# Power-Controller.net
KiCad netlist of a schematic drawn in EAGLE
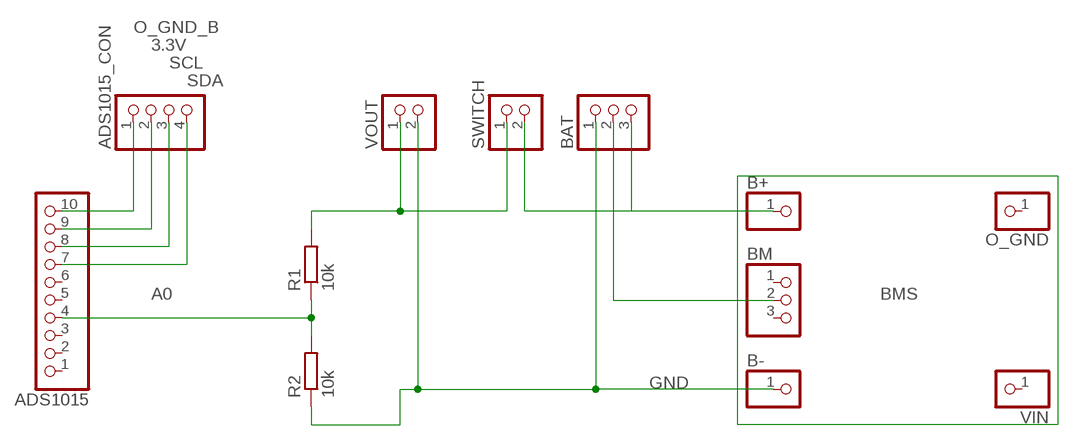
[diagram p0: schematic, sheet 1]

(export (version "E")
  (design (tool "Eeschema 10.0.6"))
  (components
    (comp (ref "ADS1015")
      (value "PINHD-1X10")
      (footprint "eagle-import:1X10")
      (libsource (lib "eagle-import") (part "PINHD-1X10"))
    )
    (comp (ref "ADS1015_CON")
      (value "PINHD-1X4/90")
      (footprint "eagle-import:1X04_90")
      (libsource (lib "eagle-import") (part "PINHD-1X4/90"))
    )
    (comp (ref "B+")
      (value "PINHD-1X1")
      (footprint "eagle-import:1X01")
      (libsource (lib "eagle-import") (part "PINHD-1X1"))
    )
    (comp (ref "B-")
      (value "PINHD-1X1")
      (footprint "eagle-import:1X01")
      (libsource (lib "eagle-import") (part "PINHD-1X1"))
    )
    (comp (ref "BAT")
      (value "PINHD-1X3/90")
      (footprint "eagle-import:1X03_90")
      (libsource (lib "eagle-import") (part "PINHD-1X3/90"))
    )
    (comp (ref "BM")
      (value "PINHD-1X3")
      (footprint "eagle-import:1X03")
      (libsource (lib "eagle-import") (part "PINHD-1X3"))
    )
    (comp (ref "O_GND")
      (value "PINHD-1X1")
      (footprint "eagle-import:1X01")
      (libsource (lib "eagle-import") (part "PINHD-1X1"))
    )
    (comp (ref "R1")
      (value "10k")
      (footprint "eagle-import:0204_7")
      (libsource (lib "eagle-import") (part "R-EU_0204/7"))
    )
    (comp (ref "R2")
      (value "10k")
      (footprint "eagle-import:0204_7")
      (libsource (lib "eagle-import") (part "R-EU_0204/7"))
    )
    (comp (ref "SWITCH")
      (value "PINHD-1X2")
      (footprint "eagle-import:1X02")
      (libsource (lib "eagle-import") (part "PINHD-1X2"))
    )
    (comp (ref "VIN")
      (value "PINHD-1X1")
      (footprint "eagle-import:1X01")
      (libsource (lib "eagle-import") (part "PINHD-1X1"))
    )
    (comp (ref "VOUT")
      (value "PINHD-1X2/90")
      (footprint "eagle-import:1X02_90")
      (libsource (lib "eagle-import") (part "PINHD-1X2/90"))
    )
  )
  (nets
    (net (code "1") (name "/3.3V") (class "Default")
      (node (ref "ADS1015") (pin "9") (pinfunction "9_9") (pintype "passive"))
      (node (ref "ADS1015_CON") (pin "2") (pinfunction "2_2") (pintype "passive"))
    )
    (net (code "2") (name "/A0") (class "Default")
      (node (ref "ADS1015") (pin "4") (pinfunction "4_4") (pintype "passive"))
      (node (ref "R1") (pin "1") (pinfunction "1_1") (pintype "passive"))
      (node (ref "R2") (pin "2") (pinfunction "2_2") (pintype "passive"))
    )
    (net (code "4") (name "/GND") (class "Default")
      (node (ref "B-") (pin "1") (pinfunction "1_1") (pintype "passive"))
      (node (ref "BAT") (pin "1") (pinfunction "1_1") (pintype "passive"))
      (node (ref "R2") (pin "1") (pinfunction "1_1") (pintype "passive"))
      (node (ref "VOUT") (pin "2") (pinfunction "2_2") (pintype "passive"))
    )
    (net (code "5") (name "/O_GND_B") (class "Default")
      (node (ref "ADS1015") (pin "10") (pinfunction "10_10") (pintype "passive"))
      (node (ref "ADS1015_CON") (pin "1") (pinfunction "1_1") (pintype "passive"))
    )
    (net (code "6") (name "/SCL") (class "Default")
      (node (ref "ADS1015") (pin "8") (pinfunction "8_8") (pintype "passive"))
      (node (ref "ADS1015_CON") (pin "3") (pinfunction "3_3") (pintype "passive"))
    )
    (net (code "7") (name "/SDA") (class "Default")
      (node (ref "ADS1015") (pin "7") (pinfunction "7_7") (pintype "passive"))
      (node (ref "ADS1015_CON") (pin "4") (pinfunction "4_4") (pintype "passive"))
    )
    (net (code "8") (name "Net-(B+-Pad1)") (class "Default")
      (node (ref "B+") (pin "1") (pinfunction "1_1") (pintype "passive"))
      (node (ref "BAT") (pin "3") (pinfunction "3_3") (pintype "passive"))
      (node (ref "SWITCH") (pin "2") (pinfunction "2_2") (pintype "passive"))
    )
    (net (code "9") (name "Net-(BAT-Pad2)") (class "Default")
      (node (ref "BAT") (pin "2") (pinfunction "2_2") (pintype "passive"))
      (node (ref "BM") (pin "2") (pinfunction "2_2") (pintype "passive"))
    )
    (net (code "10") (name "Net-(R1-Pad2)") (class "Default")
      (node (ref "R1") (pin "2") (pinfunction "2_2") (pintype "passive"))
      (node (ref "SWITCH") (pin "1") (pinfunction "1_1") (pintype "passive"))
      (node (ref "VOUT") (pin "1") (pinfunction "1_1") (pintype "passive"))
    )
    (net (code "11") (name "unconnected-(ADS1015-Pad1)") (class "Default")
      (node (ref "ADS1015") (pin "1") (pinfunction "1_1") (pintype "passive"))
    )
    (net (code "12") (name "unconnected-(ADS1015-Pad2)") (class "Default")
      (node (ref "ADS1015") (pin "2") (pinfunction "2_2") (pintype "passive"))
    )
    (net (code "13") (name "unconnected-(ADS1015-Pad3)") (class "Default")
      (node (ref "ADS1015") (pin "3") (pinfunction "3_3") (pintype "passive"))
    )
    (net (code "14") (name "unconnected-(ADS1015-Pad5)") (class "Default")
      (node (ref "ADS1015") (pin "5") (pinfunction "5_5") (pintype "passive"))
    )
    (net (code "15") (name "unconnected-(ADS1015-Pad6)") (class "Default")
      (node (ref "ADS1015") (pin "6") (pinfunction "6_6") (pintype "passive"))
    )
    (net (code "16") (name "unconnected-(BM-Pad1)") (class "Default")
      (node (ref "BM") (pin "1") (pinfunction "1_1") (pintype "passive"))
    )
    (net (code "17") (name "unconnected-(BM-Pad3)") (class "Default")
      (node (ref "BM") (pin "3") (pinfunction "3_3") (pintype "passive"))
    )
    (net (code "18") (name "unconnected-(O_GND-Pad1)") (class "Default")
      (node (ref "O_GND") (pin "1") (pinfunction "1_1") (pintype "passive"))
    )
    (net (code "19") (name "unconnected-(VIN-Pad1)") (class "Default")
      (node (ref "VIN") (pin "1") (pinfunction "1_1") (pintype "passive"))
    )
  )
)
